# FinalProjectMM.net
KiCad netlist of a schematic drawn in EAGLE
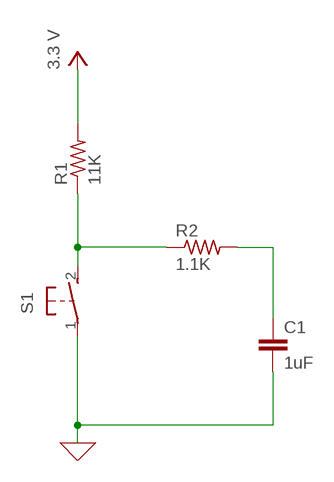
[diagram p0: schematic, sheet 1]

(export (version "E")
  (design (tool "Eeschema 10.0.6"))
  (components
    (comp (ref "C1")
      (value "1uF")
      (footprint "eagle-import:C2.5-3")
      (libsource (lib "eagle-import") (part "C2,5-3"))
    )
    (comp (ref "R1")
      (value "11K")
      (footprint "eagle-import:0204V")
      (libsource (lib "eagle-import") (part "R-US_0204/2V"))
    )
    (comp (ref "R2")
      (value "1.1K")
      (footprint "eagle-import:0204V")
      (libsource (lib "eagle-import") (part "R-US_0204/2V"))
    )
    (comp (ref "S1")
      (value "31-XX")
      (footprint "eagle-import:B3F-31XX")
      (fields (field (name "MPN") "B3F-3100"))
      (libsource (lib "eagle-import") (part "31-XX"))
    )
  )
  (nets
    (net (code "1") (name "3.3 V") (class "Default")
      (node (ref "R1") (pin "2") (pinfunction "2_2") (pintype "passive"))
    )
    (net (code "2") (name "GND") (class "Default")
      (node (ref "C1") (pin "2") (pinfunction "2_2") (pintype "passive"))
      (node (ref "S1") (pin "1") (pinfunction "P_1") (pintype "passive"))
    )
    (net (code "3") (name "Net-(C1-Pad1)") (class "Default")
      (node (ref "C1") (pin "1") (pinfunction "1_1") (pintype "passive"))
      (node (ref "R2") (pin "2") (pinfunction "2_2") (pintype "passive"))
    )
    (net (code "4") (name "Net-(S1-S)") (class "Default")
      (node (ref "R1") (pin "1") (pinfunction "1_1") (pintype "passive"))
      (node (ref "R2") (pin "1") (pinfunction "1_1") (pintype "passive"))
      (node (ref "S1") (pin "2") (pinfunction "S_2") (pintype "passive"))
    )
  )
)
